# PrintNC_CNC_Breakout.net
KiCad netlist of a schematic drawn in Altium Designer
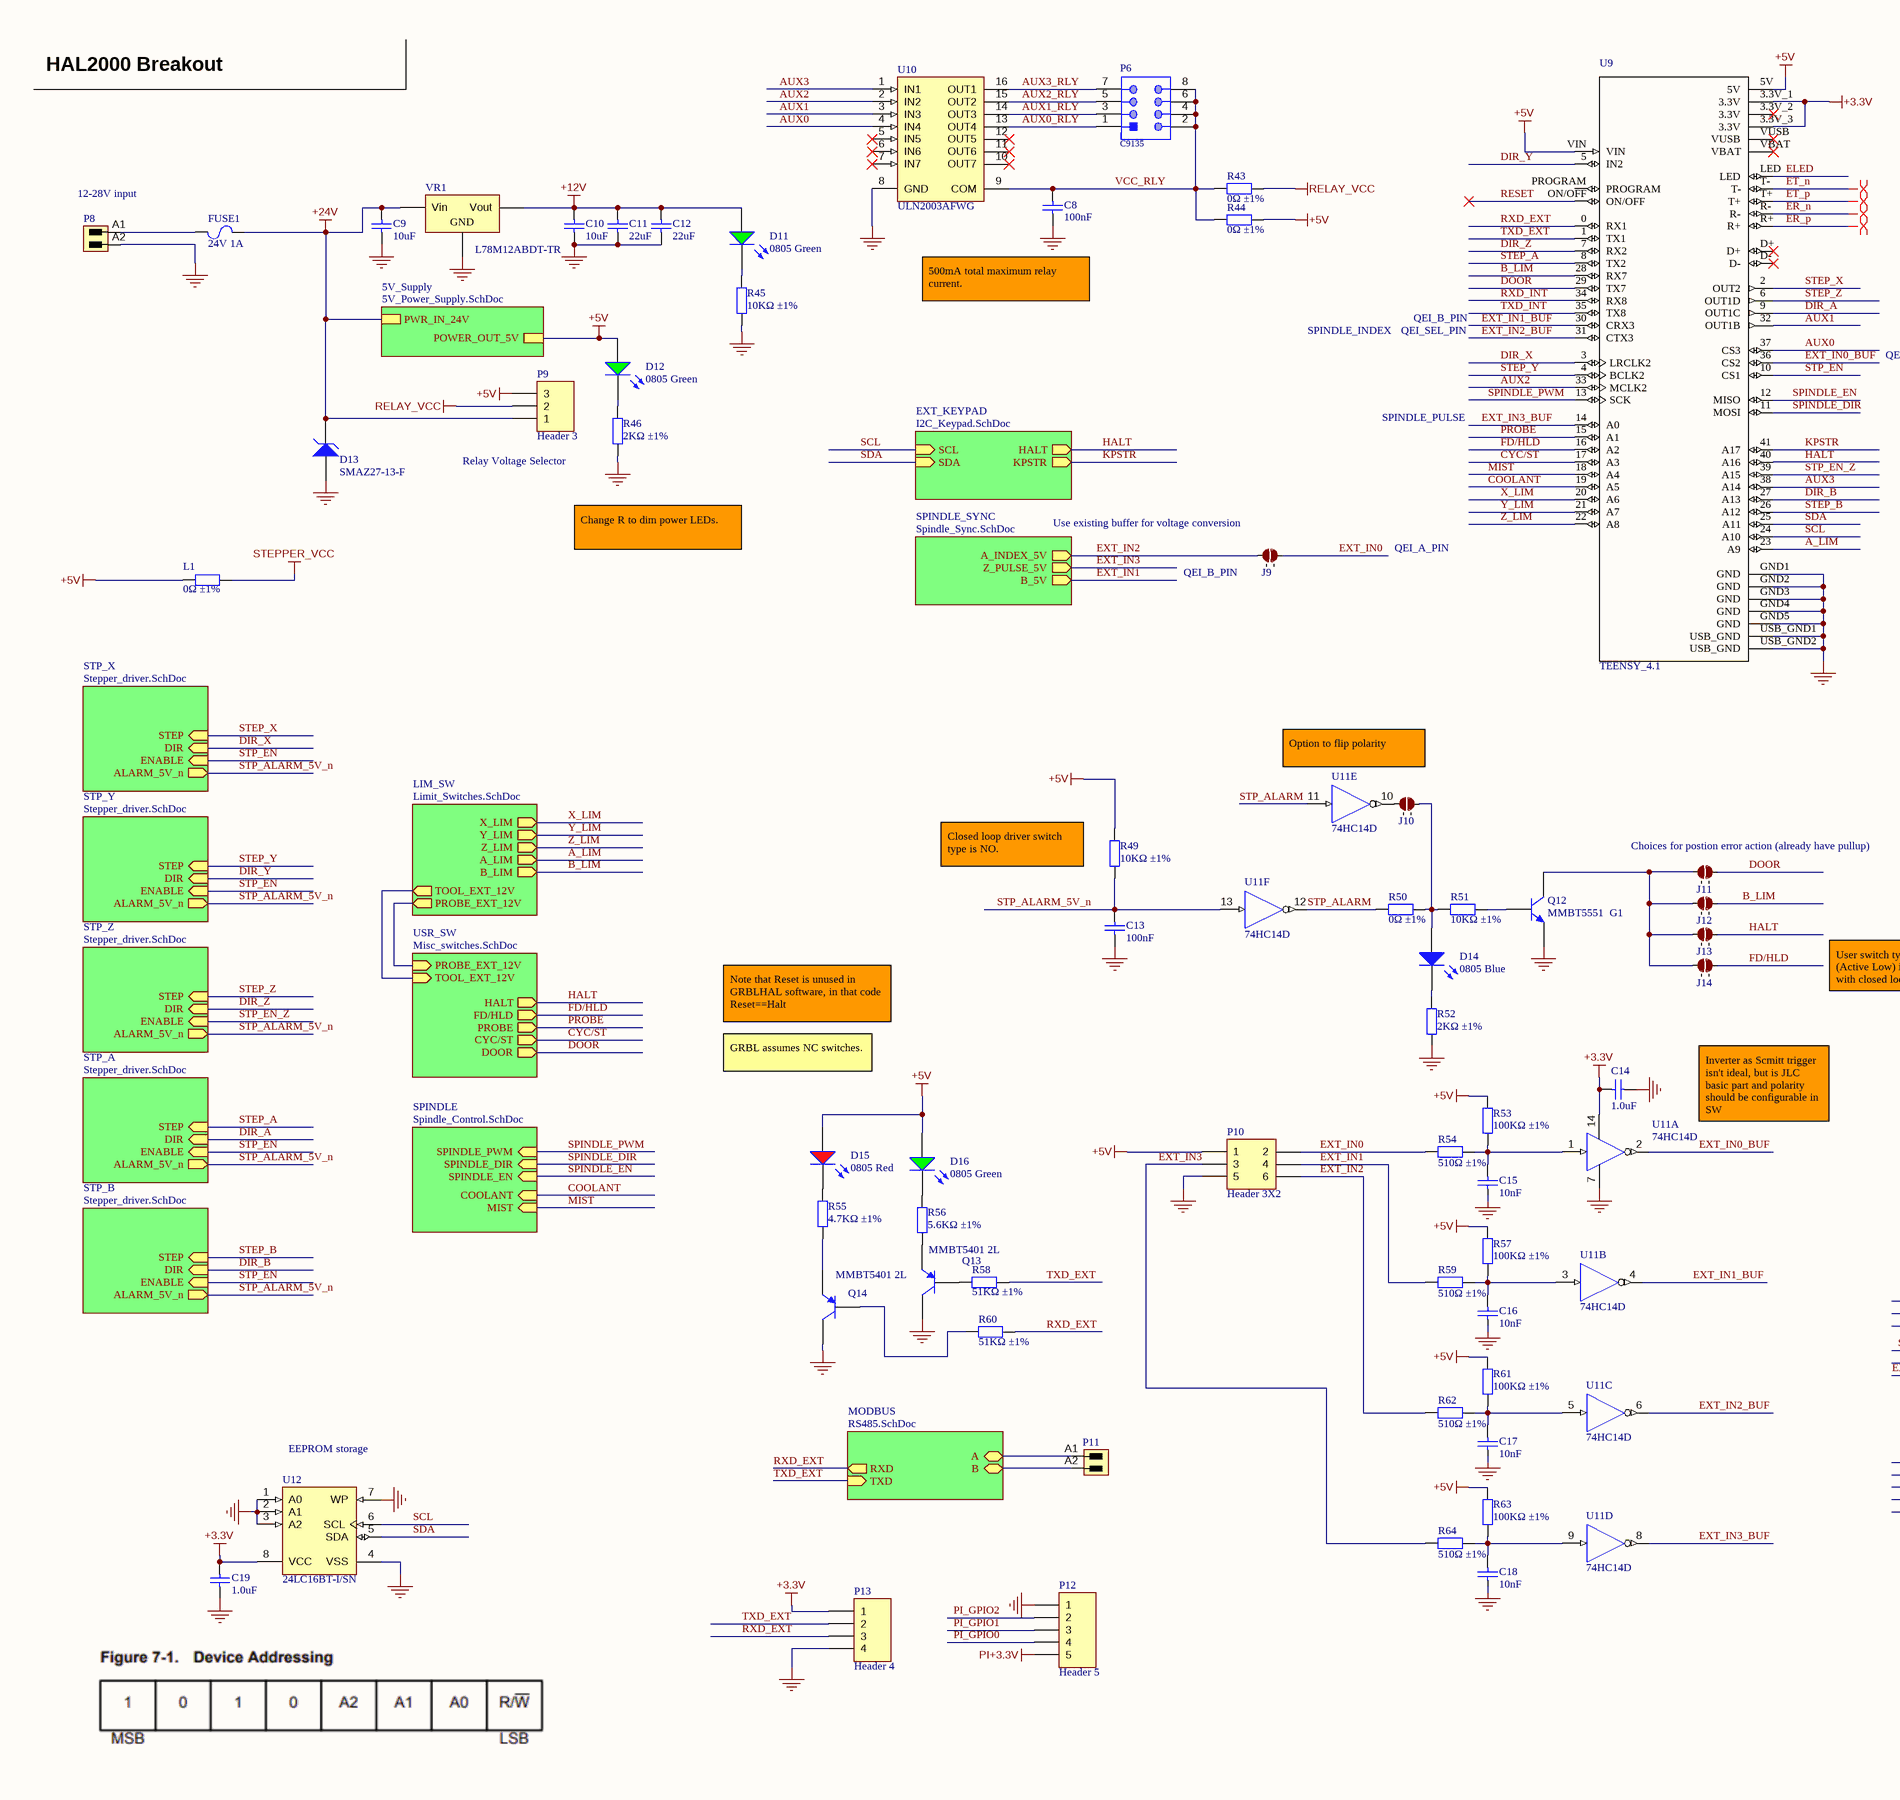
[diagram p0: PrintNC_CNC_Breakout.SchDoc, left]
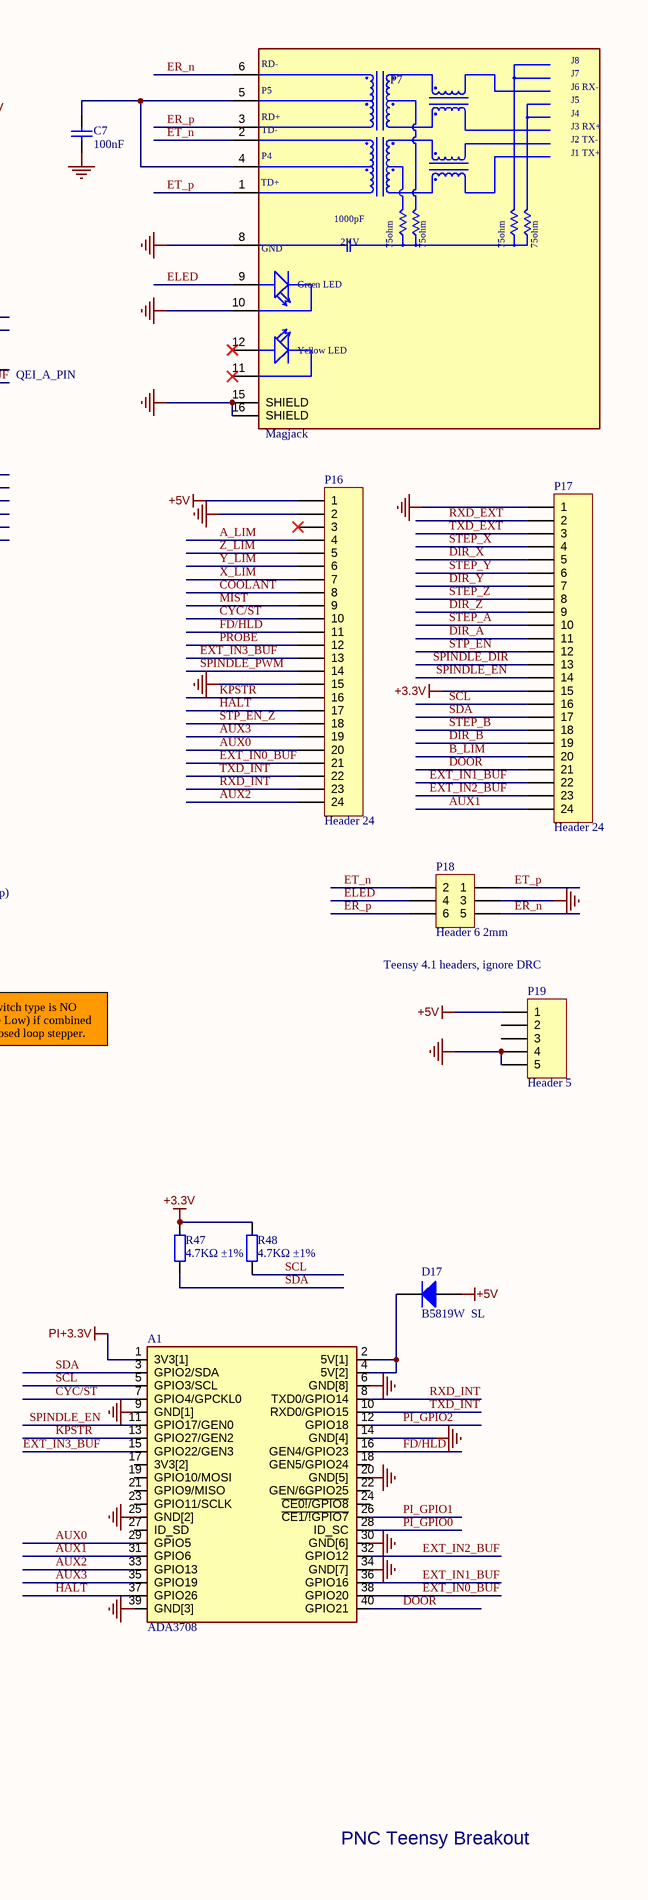
[diagram p1: PrintNC_CNC_Breakout.SchDoc, right]

(export (version "E")
  (design (tool "Eeschema 10.0.6"))
  (components
    (comp (ref "A1")
      (value "ADA3708")
      (footprint "ADA3708_RPI-ZERO")
      (description "Raspberry Pi Zero WH _Zero W with Headers_")
      (fields (field (name "MF") "Raspberry Pi"))
      (libsource (lib "Universal_CNC_Breakout") (part "ADA3708"))
    )
    (comp (ref "C7")
      (value "100nF")
      (footprint "1206_C")
      (description "Chip capacitors")
      (fields
        (field (name "MANUFACTURER") "Samsung Electro-Mechanics")
        (field (name "PARTNUMBER") "CL31B104KBCNNNC")
      )
      (libsource (lib "Cap") (part "1206 100nF (104) 10% 50V"))
    )
    (comp (ref "C8")
      (value "100nF")
      (footprint "0603_C")
      (description "Chip capacitors")
      (fields (field (name "MANUFACTURER") "YAGEO") (field (name "PARTNUMBER") "CC0603KRX7R9BB104"))
      (libsource (lib "Cap") (part "0603 100nF (104) 10% 50V"))
    )
    (comp (ref "C9")
      (value "10uF")
      (footprint "1206_C")
      (description "Chip capacitors")
      (fields
        (field (name "MANUFACTURER") "Samsung Electro-Mechanics")
        (field (name "PARTNUMBER") "CL31A106KBHNNNE")
      )
      (libsource (lib "Cap") (part "1206 10uF (106) 10% 50V"))
    )
    (comp (ref "C10")
      (value "10uF")
      (footprint "1206_C")
      (description "Chip capacitors")
      (fields
        (field (name "MANUFACTURER") "Samsung Electro-Mechanics")
        (field (name "PARTNUMBER") "CL31A106KBHNNNE")
      )
      (libsource (lib "Cap") (part "1206 10uF (106) 10% 50V"))
    )
    (comp (ref "C11")
      (value "22uF")
      (footprint "0805_C")
      (description "Chip capacitors")
      (fields
        (field (name "MANUFACTURER") "Samsung Electro-Mechanics")
        (field (name "PARTNUMBER") "CL21A226MAQNNNE")
      )
      (libsource (lib "Cap") (part "0805 22uF (226) 20% 25V"))
    )
    (comp (ref "C12")
      (value "22uF")
      (footprint "0805_C")
      (description "Chip capacitors")
      (fields
        (field (name "MANUFACTURER") "Samsung Electro-Mechanics")
        (field (name "PARTNUMBER") "CL21A226MAQNNNE")
      )
      (libsource (lib "Cap") (part "0805 22uF (226) 20% 25V"))
    )
    (comp (ref "C13")
      (value "100nF")
      (footprint "0402_C")
      (description "Chip capacitors")
      (fields
        (field (name "MANUFACTURER") "Samsung Electro-Mechanics")
        (field (name "PARTNUMBER") "CL05B104KO5NNNC")
      )
      (libsource (lib "Cap") (part "0402 100nF (104) 10% 16V"))
    )
    (comp (ref "C14")
      (value "1.0uF")
      (footprint "0402_C")
      (description "Chip capacitor")
      (fields
        (field (name "MANUFACTURER") "Samsung Electro-Mechanics")
        (field (name "PARTNUMBER") "CL05A105KA5NQNC")
      )
      (libsource (lib "Cap") (part "0402 1.0uF (105) 10% 25V"))
    )
    (comp (ref "C15")
      (value "10nF")
      (footprint "0402_C")
      (description "Chip capacitors")
      (fields
        (field (name "MANUFACTURER") "Samsung Electro-Mechanics")
        (field (name "PARTNUMBER") "CL05B103KB5NNNC")
      )
      (libsource (lib "Cap") (part "0402 10nF (103) 10% 50V"))
    )
    (comp (ref "C16")
      (value "10nF")
      (footprint "0402_C")
      (description "Chip capacitors")
      (fields
        (field (name "MANUFACTURER") "Samsung Electro-Mechanics")
        (field (name "PARTNUMBER") "CL05B103KB5NNNC")
      )
      (libsource (lib "Cap") (part "0402 10nF (103) 10% 50V"))
    )
    (comp (ref "C17")
      (value "10nF")
      (footprint "0402_C")
      (description "Chip capacitors")
      (fields
        (field (name "MANUFACTURER") "Samsung Electro-Mechanics")
        (field (name "PARTNUMBER") "CL05B103KB5NNNC")
      )
      (libsource (lib "Cap") (part "0402 10nF (103) 10% 50V"))
    )
    (comp (ref "C18")
      (value "10nF")
      (footprint "0402_C")
      (description "Chip capacitors")
      (fields
        (field (name "MANUFACTURER") "Samsung Electro-Mechanics")
        (field (name "PARTNUMBER") "CL05B103KB5NNNC")
      )
      (libsource (lib "Cap") (part "0402 10nF (103) 10% 50V"))
    )
    (comp (ref "C19")
      (value "1.0uF")
      (footprint "0402_C")
      (description "Chip capacitor")
      (fields
        (field (name "MANUFACTURER") "Samsung Electro-Mechanics")
        (field (name "PARTNUMBER") "CL05A105KA5NQNC")
      )
      (libsource (lib "Cap") (part "0402 1.0uF (105) 10% 25V"))
    )
    (comp (ref "D11")
      (value "0805 Green")
      (footprint "0805_LED_S1")
      (description "LED")
      (libsource (lib "LED") (part "0805 LED Green"))
    )
    (comp (ref "D12")
      (value "0805 Green")
      (footprint "0805_LED_S1")
      (description "LED")
      (libsource (lib "LED") (part "0805 LED Green"))
    )
    (comp (ref "D13")
      (value "SMAZ27-13-F")
      (footprint "DIOM5226X240N")
      (description "27V ±5% 1W 500nA @ 20.5V SMA(DO-214AC) Zener Diodes RoHS")
      (libsource (lib "PrintNC_GRBLHAL_Breakout") (part "BZT52C27"))
    )
    (comp (ref "D14")
      (value "0805 Blue")
      (footprint "0805_LED_S1")
      (description "LED")
      (libsource (lib "LED") (part "0805 LED Blue"))
    )
    (comp (ref "D15")
      (value "0805 Red")
      (footprint "0805_LED_S1")
      (description "LED")
      (fields
        (field (name "PARTNUMBER") "FC-2012HRK-620D")
        (field (name "MANUFACTURER") "Foshan NationStar Optoelectronics")
      )
      (libsource (lib "LED") (part "0805 LED Red"))
    )
    (comp (ref "D16")
      (value "0805 Green")
      (footprint "0805_LED_S1")
      (description "LED")
      (libsource (lib "LED") (part "0805 LED Green"))
    )
    (comp (ref "D17")
      (value "B5819W  SL")
      (footprint "SOD-123")
      (description "肖特基二极管")
      (libsource (lib "Diode") (part "SOD-123 B5819W  SL"))
    )
    (comp (ref "FUSE1")
      (value "24V 1A")
      (footprint "1206_C")
      (description "24V 1A 0.1s 1206 PTC Resettable Fuses RoHS")
      (fields
        (field (name "MANUFACTURER") "Jinrui Electronic Materials Co.")
        (field (name "PARTNUMBER") "JK-nSMD050-24")
      )
      (libsource (lib "PrintNC_GRBLHAL_Breakout") (part "JK-nSMD050-24"))
    )
    (comp (ref "J9")
      (value "2 way net solder junction - Normally Open")
      (footprint "2waySolder_NO")
      (libsource (lib "PrintNC_GRBLHAL_Breakout") (part "2waySolderNO"))
    )
    (comp (ref "J10")
      (value "2 way net solder junction - Normally Open")
      (footprint "2waySolder_NO")
      (libsource (lib "PrintNC_GRBLHAL_Breakout") (part "2waySolderNO"))
    )
    (comp (ref "J11")
      (value "2 way net solder junction - Normally Open")
      (footprint "2waySolder_NO")
      (libsource (lib "PrintNC_GRBLHAL_Breakout") (part "2waySolderNO"))
    )
    (comp (ref "J12")
      (value "2 way net solder junction - Normally Open")
      (footprint "2waySolder_NO")
      (libsource (lib "PrintNC_GRBLHAL_Breakout") (part "2waySolderNO"))
    )
    (comp (ref "J13")
      (value "2 way net solder junction - Normally Open")
      (footprint "2waySolder_NO")
      (libsource (lib "PrintNC_GRBLHAL_Breakout") (part "2waySolderNO"))
    )
    (comp (ref "J14")
      (value "2 way net solder junction - Normally Open")
      (footprint "2waySolder_NO")
      (libsource (lib "PrintNC_GRBLHAL_Breakout") (part "2waySolderNO"))
    )
    (comp (ref "L1")
      (value "0Ω ±1%")
      (footprint "0402_R")
      (description "Chip resistor")
      (fields (field (name "POWER") "1/16W") (field (name "MANUFACTURER") "Uniroyal Elec"))
      (libsource (lib "") (part "0402 0R (0R0) 1%_1"))
    )
    (comp (ref "P6")
      (value "C9135")
      (footprint "61200821621")
      (description "Male Box Header WR-BHD, THT, Vertical, pitch 2.54 mm, 8 pins")
      (fields (field (name "MANUFACTURER") "Wurth Elektronik") (field (name "PUBLISHER") "WurthElektronik"))
      (libsource (lib "PrintNC_GRBLHAL_Breakout") (part "WE-CN-2P-M-R8"))
    )
    (comp (ref "P7")
      (value "Magjack")
      (footprint "HANRUN_HR911105A")
      (description "HR911105A Ethernet Interface Arduino Platform Evaluation Expansion Board")
      (fields (field (name "MP") "HR911105A") (field (name "MF") "DFRobot"))
      (libsource (lib "PrintNC_GRBLHAL_Breakout") (part "HR911105A"))
    )
    (comp (ref "P8")
      (value "~")
      (footprint "SL_3_50_180G_02")
      (fields
        (field (name "PARTNUMBER") "WJ15EDGVC-3.5-2P")
        (field (name "MANUFACTURER") "Ningbo Kangnex Elec")
      )
      (libsource (lib "") (part "Header_Male_02_1x02_1"))
    )
    (comp (ref "P9")
      (value "Header 3")
      (footprint "HDR1X3")
      (description "Header, 3-Pin")
      (fields (field (name "PUBLISHER") "Altium Limited"))
      (libsource (lib "PrintNC_GRBLHAL_Breakout") (part "Header 3"))
    )
    (comp (ref "P10")
      (value "Header 3X2")
      (footprint "HDR2X3")
      (description "Header, 3-Pin, Dual row")
      (fields (field (name "PUBLISHER") "Altium Limited"))
      (libsource (lib "PrintNC_GRBLHAL_Breakout") (part "Header 3X2"))
    )
    (comp (ref "P11")
      (value "~")
      (footprint "SL_3_50_180G_02")
      (fields
        (field (name "PARTNUMBER") "WJ15EDGVC-3.5-2P")
        (field (name "MANUFACTURER") "Ningbo Kangnex Elec")
      )
      (libsource (lib "PrintNC_GRBLHAL_Breakout") (part "Header_Male_02_1x02"))
    )
    (comp (ref "P12")
      (value "Header 5")
      (footprint "HDR1X5")
      (description "Header, 5-Pin")
      (fields (field (name "PUBLISHER") "Altium Limited"))
      (libsource (lib "PrintNC_GRBLHAL_Breakout") (part "Header 5"))
    )
    (comp (ref "P13")
      (value "Header 4")
      (footprint "HDR1X4")
      (description "Header, 4-Pin")
      (fields (field (name "PUBLISHER") "Altium Limited"))
      (libsource (lib "PrintNC_GRBLHAL_Breakout") (part "Header 4"))
    )
    (comp (ref "P16")
      (value "Header 24")
      (footprint "HDR1X24")
      (description "Header, 24-Pin")
      (fields (field (name "PUBLISHER") "Altium Limited"))
      (libsource (lib "Miscellaneous Connectors") (part "Header 24"))
    )
    (comp (ref "P17")
      (value "Header 24")
      (footprint "HDR1X24")
      (description "Header, 24-Pin")
      (fields (field (name "PUBLISHER") "Altium Limited"))
      (libsource (lib "Miscellaneous Connectors") (part "Header 24"))
    )
    (comp (ref "P18")
      (value "Header 6 2mm")
      (footprint "HDR2X3 - 2mm")
      (description "Header, 6-Pin 2x3, 2mm pitch")
      (fields (field (name "PUBLISHER") "Altium Limited"))
      (libsource (lib "PrintNC_GRBLHAL_Breakout") (part "Header 6 2mm"))
    )
    (comp (ref "P19")
      (value "Header 5")
      (footprint "HDR1X5")
      (description "Header, 5-Pin")
      (fields (field (name "PUBLISHER") "Altium Limited"))
      (libsource (lib "PrintNC_GRBLHAL_Breakout") (part "Header 5"))
    )
    (comp (ref "Q12")
      (value "MMBT5551  G1")
      (footprint "SOT-23(SOT-23-3)")
      (description "三极管")
      (libsource (lib "PrintNC_GRBLHAL_Breakout") (part "SOT-23 MMBT5551  G1"))
    )
    (comp (ref "Q13")
      (value "MMBT5401 2L")
      (footprint "SOT-23(SOT-23-3)")
      (description "三极管")
      (libsource (lib "PrintNC_GRBLHAL_Breakout") (part "SOT-23 MMBT5401 2L"))
    )
    (comp (ref "Q14")
      (value "MMBT5401 2L")
      (footprint "SOT-23(SOT-23-3)")
      (description "三极管")
      (libsource (lib "PrintNC_GRBLHAL_Breakout") (part "SOT-23 MMBT5401 2L"))
    )
    (comp (ref "R43")
      (value "0Ω ±1%")
      (footprint "0402_R")
      (description "Chip resistor")
      (fields (field (name "POWER") "1/16W") (field (name "MANUFACTURER") "Uniroyal Elec"))
      (libsource (lib "PrintNC_GRBLHAL_Breakout") (part "0402 0R (0R0) 1%"))
    )
    (comp (ref "R44")
      (value "0Ω ±1%")
      (footprint "0402_R")
      (description "Chip resistor")
      (fields (field (name "POWER") "1/16W") (field (name "MANUFACTURER") "Uniroyal Elec"))
      (libsource (lib "PrintNC_GRBLHAL_Breakout") (part "0402 0R (0R0) 1%"))
    )
    (comp (ref "R45")
      (value "10KΩ ±1%")
      (footprint "0402_R")
      (description "Chip resistor")
      (fields (field (name "MANUFACTURER") "Uniroyal Elec") (field (name "PARTNUMBER") "0402WGF1002TCE"))
      (libsource (lib "PrintNC_GRBLHAL_Breakout") (part "0402 10K (1002) 1%"))
    )
    (comp (ref "R46")
      (value "2KΩ ±1%")
      (footprint "0402_R")
      (description "Chip resistor")
      (fields (field (name "MANUFACTURER") "Uniroyal Elec") (field (name "PARTNUMBER") "0402WGF2001TCE"))
      (libsource (lib "RES") (part "0402 2K (2001) 1%"))
    )
    (comp (ref "R47")
      (value "4.7KΩ ±1%")
      (footprint "0402_R")
      (description "Chip resistor")
      (fields (field (name "MANUFACTURER") "Uniroyal Elec") (field (name "PARTNUMBER") "0402WGF4701TCE"))
      (libsource (lib "RES") (part "0402 4.7K (4701) 1%"))
    )
    (comp (ref "R48")
      (value "4.7KΩ ±1%")
      (footprint "0402_R")
      (description "Chip resistor")
      (fields (field (name "MANUFACTURER") "Uniroyal Elec") (field (name "PARTNUMBER") "0402WGF4701TCE"))
      (libsource (lib "RES") (part "0402 4.7K (4701) 1%"))
    )
    (comp (ref "R49")
      (value "10KΩ ±1%")
      (footprint "0402_R")
      (description "Chip resistor")
      (fields (field (name "MANUFACTURER") "Uniroyal Elec") (field (name "PARTNUMBER") "0402WGF1002TCE"))
      (libsource (lib "PrintNC_GRBLHAL_Breakout") (part "0402 10K (1002) 1%"))
    )
    (comp (ref "R50")
      (value "0Ω ±1%")
      (footprint "0402_R")
      (description "Chip resistor")
      (fields (field (name "POWER") "1/16W") (field (name "MANUFACTURER") "Uniroyal Elec"))
      (libsource (lib "PrintNC_GRBLHAL_Breakout") (part "0402 0R (0R0) 1%"))
    )
    (comp (ref "R51")
      (value "10KΩ ±1%")
      (footprint "0402_R")
      (description "Chip resistor")
      (fields (field (name "MANUFACTURER") "Uniroyal Elec") (field (name "PARTNUMBER") "0402WGF1002TCE"))
      (libsource (lib "") (part "0402 10K (1002) 1%_1"))
    )
    (comp (ref "R52")
      (value "2KΩ ±1%")
      (footprint "0402_R")
      (description "Chip resistor")
      (fields (field (name "MANUFACTURER") "Uniroyal Elec") (field (name "PARTNUMBER") "0402WGF2001TCE"))
      (libsource (lib "PrintNC_GRBLHAL_Breakout") (part "0402 2K (2001) 1%"))
    )
    (comp (ref "R53")
      (value "100KΩ ±1%")
      (footprint "0402_R")
      (description "Chip resistor")
      (fields (field (name "MANUFACTURER") "Uniroyal Elec") (field (name "PARTNUMBER") "0402WGF1003TCE"))
      (libsource (lib "PrintNC_GRBLHAL_Breakout") (part "0402 100K (1003) 1%"))
    )
    (comp (ref "R54")
      (value "510Ω ±1%")
      (footprint "0402_R")
      (description "Chip resistor")
      (fields (field (name "MANUFACTURER") "Uniroyal Elec") (field (name "PARTNUMBER") "0402WGF5100TCE"))
      (libsource (lib "PrintNC_GRBLHAL_Breakout") (part "0402 510R (5100) 1%"))
    )
    (comp (ref "R55")
      (value "4.7KΩ ±1%")
      (footprint "0402_R")
      (description "Chip resistor")
      (fields (field (name "MANUFACTURER") "Uniroyal Elec") (field (name "PARTNUMBER") "0402WGF4701TCE"))
      (libsource (lib "PrintNC_GRBLHAL_Breakout") (part "0402 4.7K (4701) 1%"))
    )
    (comp (ref "R56")
      (value "5.6KΩ ±1%")
      (footprint "0402_R")
      (description "Chip resistor")
      (fields (field (name "MANUFACTURER") "Uniroyal Elec") (field (name "PARTNUMBER") "0402WGF5601TCE"))
      (libsource (lib "PrintNC_GRBLHAL_Breakout") (part "0402 5.6K (5601) 1%"))
    )
    (comp (ref "R57")
      (value "100KΩ ±1%")
      (footprint "0402_R")
      (description "Chip resistor")
      (fields (field (name "MANUFACTURER") "Uniroyal Elec") (field (name "PARTNUMBER") "0402WGF1003TCE"))
      (libsource (lib "PrintNC_GRBLHAL_Breakout") (part "0402 100K (1003) 1%"))
    )
    (comp (ref "R58")
      (value "51KΩ ±1%")
      (footprint "0402_R")
      (description "Chip resistor")
      (fields (field (name "MANUFACTURER") "Uniroyal Elec") (field (name "PARTNUMBER") "0402WGF5102TCE"))
      (libsource (lib "PrintNC_GRBLHAL_Breakout") (part "0402 51K (5102) 1%"))
    )
    (comp (ref "R59")
      (value "510Ω ±1%")
      (footprint "0402_R")
      (description "Chip resistor")
      (fields (field (name "MANUFACTURER") "Uniroyal Elec") (field (name "PARTNUMBER") "0402WGF5100TCE"))
      (libsource (lib "PrintNC_GRBLHAL_Breakout") (part "0402 510R (5100) 1%"))
    )
    (comp (ref "R60")
      (value "51KΩ ±1%")
      (footprint "0402_R")
      (description "Chip resistor")
      (fields (field (name "MANUFACTURER") "Uniroyal Elec") (field (name "PARTNUMBER") "0402WGF5102TCE"))
      (libsource (lib "") (part "0402 51K (5102) 1%_1"))
    )
    (comp (ref "R61")
      (value "100KΩ ±1%")
      (footprint "0402_R")
      (description "Chip resistor")
      (fields (field (name "MANUFACTURER") "Uniroyal Elec") (field (name "PARTNUMBER") "0402WGF1003TCE"))
      (libsource (lib "PrintNC_GRBLHAL_Breakout") (part "0402 100K (1003) 1%"))
    )
    (comp (ref "R62")
      (value "510Ω ±1%")
      (footprint "0402_R")
      (description "Chip resistor")
      (fields (field (name "MANUFACTURER") "Uniroyal Elec") (field (name "PARTNUMBER") "0402WGF5100TCE"))
      (libsource (lib "PrintNC_GRBLHAL_Breakout") (part "0402 510R (5100) 1%"))
    )
    (comp (ref "R63")
      (value "100KΩ ±1%")
      (footprint "0402_R")
      (description "Chip resistor")
      (fields (field (name "MANUFACTURER") "Uniroyal Elec") (field (name "PARTNUMBER") "0402WGF1003TCE"))
      (libsource (lib "PrintNC_GRBLHAL_Breakout") (part "0402 100K (1003) 1%"))
    )
    (comp (ref "R64")
      (value "510Ω ±1%")
      (footprint "0402_R")
      (description "Chip resistor")
      (fields (field (name "MANUFACTURER") "Uniroyal Elec") (field (name "PARTNUMBER") "0402WGF5100TCE"))
      (libsource (lib "PrintNC_GRBLHAL_Breakout") (part "0402 510R (5100) 1%"))
    )
    (comp (ref "U9")
      (value "TEENSY_4.1")
      (footprint "TEENSY4-1")
      (description "None")
      (libsource (lib "PrintNC_GRBLHAL_Breakout") (part "DEV-16771"))
    )
    (comp (ref "U10")
      (value "ULN2003AFWG")
      (footprint "SOIC-16_150mil")
      (description "大电流驱动")
      (libsource (lib "PrintNC_GRBLHAL_Breakout") (part "ULN2003AFWG_[C5437]"))
    )
    (comp (ref "U11")
      (value "74HC14D")
      (footprint "SOIC-14_150mil")
      (description "74系列逻辑芯片")
      (libsource (lib "PrintNC_GRBLHAL_Breakout") (part "74HC14D_[C5605]"))
    )
    (comp (ref "U12")
      (value "24LC16BT-I/SN")
      (footprint "SOIC-SN8_L")
      (description "IC EEPROM 16KBIT I2C 8SOIC")
      (libsource (lib "PrintNC_GRBLHAL_Breakout") (part "MEM-SEEPROM-34AA02-IL8"))
    )
    (comp (ref "VR1")
      (value "L78M12ABDT-TR")
      (footprint "TO-252-2-180")
      (description "DNI")
      (libsource (lib "PrintNC_GRBLHAL_Breakout") (part "TO-252-2 L78M05ABDT-TR"))
    )
  )
  (nets
    (net (code "1") (name "+3.3V") (class "Default")
      (node (ref "C14") (pin "1") (pinfunction "1_1") (pintype "passive"))
      (node (ref "C19") (pin "2") (pinfunction "2_2") (pintype "passive"))
      (node (ref "P13") (pin "1") (pinfunction "1_1") (pintype "passive"))
      (node (ref "P17") (pin "15") (pinfunction "15_15") (pintype "passive"))
      (node (ref "R47") (pin "2") (pinfunction "2_2") (pintype "passive"))
      (node (ref "R48") (pin "2") (pinfunction "2_2") (pintype "passive"))
      (node (ref "U11") (pin "14") (pinfunction "VCC_14") (pintype "power_in"))
      (node (ref "U12") (pin "8") (pinfunction "VCC_8") (pintype "power_in"))
      (node (ref "U9") (pin "3.3V_1") (pinfunction "3.3V_3.3V_1") (pintype "power_in"))
      (node (ref "U9") (pin "3.3V_3") (pinfunction "3.3V_3.3V_3") (pintype "power_in"))
    )
    (net (code "2") (name "+5V") (class "Default")
      (node (ref "D12") (pin "A") (pinfunction "A_A") (pintype "passive"))
      (node (ref "D15") (pin "A") (pinfunction "A_A") (pintype "passive"))
      (node (ref "D16") (pin "A") (pinfunction "A_A") (pintype "passive"))
      (node (ref "D17") (pin "1") (pinfunction "A_1") (pintype "passive"))
      (node (ref "L1") (pin "1") (pinfunction "1_1") (pintype "passive"))
      (node (ref "P10") (pin "1") (pinfunction "1_1") (pintype "passive"))
      (node (ref "P16") (pin "1") (pinfunction "1_1") (pintype "passive"))
      (node (ref "P19") (pin "1") (pinfunction "1_1") (pintype "passive"))
      (node (ref "P9") (pin "3") (pinfunction "3_3") (pintype "passive"))
      (node (ref "R44") (pin "1") (pinfunction "1_1") (pintype "passive"))
      (node (ref "R49") (pin "2") (pinfunction "2_2") (pintype "passive"))
      (node (ref "R53") (pin "2") (pinfunction "2_2") (pintype "passive"))
      (node (ref "R57") (pin "2") (pinfunction "2_2") (pintype "passive"))
      (node (ref "R61") (pin "2") (pinfunction "2_2") (pintype "passive"))
      (node (ref "R63") (pin "2") (pinfunction "2_2") (pintype "passive"))
      (node (ref "U9") (pin "5V") (pinfunction "5V_5V") (pintype "power_in"))
      (node (ref "U9") (pin "VIN") (pinfunction "VIN_VIN") (pintype "input"))
    )
    (net (code "3") (name "+12V") (class "Default")
      (node (ref "C10") (pin "2") (pinfunction "2_2") (pintype "passive"))
      (node (ref "C11") (pin "2") (pinfunction "2_2") (pintype "passive"))
      (node (ref "C12") (pin "2") (pinfunction "2_2") (pintype "passive"))
      (node (ref "D11") (pin "A") (pinfunction "A_A") (pintype "passive"))
      (node (ref "VR1") (pin "3") (pinfunction "Vout_3") (pintype "passive"))
    )
    (net (code "4") (name "+24V") (class "Default")
      (node (ref "C9") (pin "2") (pinfunction "2_2") (pintype "passive"))
      (node (ref "D13") (pin "2") (pinfunction "K_2") (pintype "passive"))
      (node (ref "FUSE1") (pin "2") (pinfunction "2_2") (pintype "passive"))
      (node (ref "P9") (pin "1") (pinfunction "1_1") (pintype "passive"))
      (node (ref "VR1") (pin "1") (pinfunction "Vin_1") (pintype "passive"))
    )
    (net (code "5") (name "/A") (class "Default")
      (node (ref "P11") (pin "A1") (pinfunction "A1_A1") (pintype "passive"))
    )
    (net (code "6") (name "/AUX0") (class "Default")
      (node (ref "A1") (pin "29") (pinfunction "GPIO5_29") (pintype "bidirectional"))
      (node (ref "P16") (pin "20") (pinfunction "20_20") (pintype "passive"))
      (node (ref "U10") (pin "4") (pinfunction "IN4_4") (pintype "input"))
      (node (ref "U9") (pin "37") (pinfunction "CS3_37") (pintype "bidirectional"))
    )
    (net (code "7") (name "/AUX0_RLY") (class "Default")
      (node (ref "P6") (pin "1") (pinfunction "1_1") (pintype "passive"))
      (node (ref "U10") (pin "13") (pinfunction "OUT4_13") (pintype "open_collector"))
    )
    (net (code "8") (name "/AUX1") (class "Default")
      (node (ref "A1") (pin "31") (pinfunction "GPIO6_31") (pintype "bidirectional"))
      (node (ref "P17") (pin "24") (pinfunction "24_24") (pintype "passive"))
      (node (ref "U10") (pin "3") (pinfunction "IN3_3") (pintype "input"))
      (node (ref "U9") (pin "32") (pinfunction "OUT1B_32") (pintype "output"))
    )
    (net (code "9") (name "/AUX1_RLY") (class "Default")
      (node (ref "P6") (pin "3") (pinfunction "3_3") (pintype "passive"))
      (node (ref "U10") (pin "14") (pinfunction "OUT3_14") (pintype "open_collector"))
    )
    (net (code "10") (name "/AUX2") (class "Default")
      (node (ref "A1") (pin "33") (pinfunction "GPIO13_33") (pintype "bidirectional"))
      (node (ref "P16") (pin "24") (pinfunction "24_24") (pintype "passive"))
      (node (ref "U10") (pin "2") (pinfunction "IN2_2") (pintype "input"))
      (node (ref "U9") (pin "33") (pinfunction "MCLK2_33") (pintype "bidirectional"))
    )
    (net (code "11") (name "/AUX2_RLY") (class "Default")
      (node (ref "P6") (pin "5") (pinfunction "5_5") (pintype "passive"))
      (node (ref "U10") (pin "15") (pinfunction "OUT2_15") (pintype "open_collector"))
    )
    (net (code "12") (name "/AUX3") (class "Default")
      (node (ref "A1") (pin "35") (pinfunction "GPIO19_35") (pintype "bidirectional"))
      (node (ref "P16") (pin "19") (pinfunction "19_19") (pintype "passive"))
      (node (ref "U10") (pin "1") (pinfunction "IN1_1") (pintype "input"))
      (node (ref "U9") (pin "38") (pinfunction "A14_38") (pintype "bidirectional"))
    )
    (net (code "13") (name "/AUX3_RLY") (class "Default")
      (node (ref "P6") (pin "7") (pinfunction "7_7") (pintype "passive"))
      (node (ref "U10") (pin "16") (pinfunction "OUT1_16") (pintype "open_collector"))
    )
    (net (code "14") (name "/A_LIM") (class "Default")
      (node (ref "P16") (pin "4") (pinfunction "4_4") (pintype "passive"))
      (node (ref "U9") (pin "23") (pinfunction "A9_23") (pintype "bidirectional"))
    )
    (net (code "15") (name "/B") (class "Default")
      (node (ref "P11") (pin "A2") (pinfunction "A2_A2") (pintype "passive"))
    )
    (net (code "16") (name "/B_LIM") (class "Default")
      (node (ref "J12") (pin "2") (pinfunction "2_2") (pintype "passive"))
      (node (ref "P17") (pin "20") (pinfunction "20_20") (pintype "passive"))
      (node (ref "U9") (pin "28") (pinfunction "RX7_28") (pintype "bidirectional"))
    )
    (net (code "17") (name "/COOLANT") (class "Default")
      (node (ref "P16") (pin "8") (pinfunction "8_8") (pintype "passive"))
      (node (ref "U9") (pin "19") (pinfunction "A5_19") (pintype "bidirectional"))
    )
    (net (code "18") (name "/CYC{slash}ST") (class "Default")
      (node (ref "A1") (pin "7") (pinfunction "GPIO4/GPCKL0_7") (pintype "bidirectional"))
      (node (ref "P16") (pin "10") (pinfunction "10_10") (pintype "passive"))
      (node (ref "U9") (pin "17") (pinfunction "A3_17") (pintype "bidirectional"))
    )
    (net (code "19") (name "/DIR_A") (class "Default")
      (node (ref "P17") (pin "11") (pinfunction "11_11") (pintype "passive"))
      (node (ref "U9") (pin "9") (pinfunction "OUT1C_9") (pintype "output"))
    )
    (net (code "20") (name "/DIR_B") (class "Default")
      (node (ref "P17") (pin "19") (pinfunction "19_19") (pintype "passive"))
      (node (ref "U9") (pin "27") (pinfunction "A13_27") (pintype "bidirectional"))
    )
    (net (code "21") (name "/DIR_X") (class "Default")
      (node (ref "P17") (pin "5") (pinfunction "5_5") (pintype "passive"))
      (node (ref "U9") (pin "3") (pinfunction "LRCLK2_3") (pintype "bidirectional"))
    )
    (net (code "22") (name "/DIR_Y") (class "Default")
      (node (ref "P17") (pin "7") (pinfunction "7_7") (pintype "passive"))
      (node (ref "U9") (pin "5") (pinfunction "IN2_5") (pintype "bidirectional"))
    )
    (net (code "23") (name "/DIR_Z") (class "Default")
      (node (ref "P17") (pin "9") (pinfunction "9_9") (pintype "passive"))
      (node (ref "U9") (pin "7") (pinfunction "RX2_7") (pintype "bidirectional"))
    )
    (net (code "24") (name "/DOOR") (class "Default")
      (node (ref "A1") (pin "40") (pinfunction "GPIO21_40") (pintype "bidirectional"))
      (node (ref "J11") (pin "2") (pinfunction "2_2") (pintype "passive"))
      (node (ref "P17") (pin "21") (pinfunction "21_21") (pintype "passive"))
      (node (ref "U9") (pin "29") (pinfunction "TX7_29") (pintype "bidirectional"))
    )
    (net (code "25") (name "/ELED") (class "Default")
      (node (ref "P18") (pin "4") (pinfunction "4_4") (pintype "passive"))
      (node (ref "P7") (pin "9") (pinfunction "GA_9") (pintype "passive"))
      (node (ref "U9") (pin "LED") (pinfunction "LED_LED") (pintype "bidirectional"))
    )
    (net (code "26") (name "/ER_n") (class "Default")
      (node (ref "P18") (pin "5") (pinfunction "5_5") (pintype "passive"))
      (node (ref "P7") (pin "6") (pinfunction "RD-_6") (pintype "passive"))
      (node (ref "U9") (pin "R-") (pinfunction "R-_R-") (pintype "bidirectional"))
    )
    (net (code "27") (name "/ER_p") (class "Default")
      (node (ref "P18") (pin "6") (pinfunction "6_6") (pintype "passive"))
      (node (ref "P7") (pin "3") (pinfunction "RD+_3") (pintype "passive"))
      (node (ref "U9") (pin "R+") (pinfunction "R+_R+") (pintype "bidirectional"))
    )
    (net (code "28") (name "/ET_n") (class "Default")
      (node (ref "P18") (pin "2") (pinfunction "2_2") (pintype "passive"))
      (node (ref "P7") (pin "2") (pinfunction "TD-_2") (pintype "passive"))
      (node (ref "U9") (pin "T-") (pinfunction "T-_T-") (pintype "bidirectional"))
    )
    (net (code "29") (name "/ET_p") (class "Default")
      (node (ref "P18") (pin "1") (pinfunction "1_1") (pintype "passive"))
      (node (ref "P7") (pin "1") (pinfunction "TD+_1") (pintype "passive"))
      (node (ref "U9") (pin "T+") (pinfunction "T+_T+") (pintype "bidirectional"))
    )
    (net (code "30") (name "/EXT_IN0") (class "Default")
      (node (ref "J9") (pin "2") (pinfunction "2_2") (pintype "passive"))
      (node (ref "P10") (pin "2") (pinfunction "2_2") (pintype "passive"))
      (node (ref "R54") (pin "1") (pinfunction "1_1") (pintype "passive"))
    )
    (net (code "31") (name "/EXT_IN0_BUF") (class "Default")
      (node (ref "A1") (pin "38") (pinfunction "GPIO20_38") (pintype "bidirectional"))
      (node (ref "P16") (pin "21") (pinfunction "21_21") (pintype "passive"))
      (node (ref "U11") (pin "2") (pinfunction "Y_2") (pintype "output"))
      (node (ref "U9") (pin "36") (pinfunction "CS2_36") (pintype "bidirectional"))
    )
    (net (code "32") (name "/EXT_IN1") (class "Default")
      (node (ref "P10") (pin "4") (pinfunction "4_4") (pintype "passive"))
      (node (ref "R59") (pin "1") (pinfunction "1_1") (pintype "passive"))
    )
    (net (code "33") (name "/EXT_IN1_BUF") (class "Default")
      (node (ref "A1") (pin "36") (pinfunction "GPIO16_36") (pintype "bidirectional"))
      (node (ref "P17") (pin "22") (pinfunction "22_22") (pintype "passive"))
      (node (ref "U11") (pin "4") (pinfunction "Y_4") (pintype "output"))
      (node (ref "U9") (pin "30") (pinfunction "CRX3_30") (pintype "bidirectional"))
    )
    (net (code "34") (name "/EXT_IN2") (class "Default")
      (node (ref "J9") (pin "1") (pinfunction "1_1") (pintype "passive"))
      (node (ref "P10") (pin "6") (pinfunction "6_6") (pintype "passive"))
      (node (ref "R62") (pin "1") (pinfunction "1_1") (pintype "passive"))
    )
    (net (code "35") (name "/EXT_IN2_BUF") (class "Default")
      (node (ref "A1") (pin "32") (pinfunction "GPIO12_32") (pintype "bidirectional"))
      (node (ref "P17") (pin "23") (pinfunction "23_23") (pintype "passive"))
      (node (ref "U11") (pin "6") (pinfunction "Y_6") (pintype "output"))
      (node (ref "U9") (pin "31") (pinfunction "CTX3_31") (pintype "bidirectional"))
    )
    (net (code "36") (name "/EXT_IN3") (class "Default")
      (node (ref "P10") (pin "3") (pinfunction "3_3") (pintype "passive"))
      (node (ref "R64") (pin "1") (pinfunction "1_1") (pintype "passive"))
    )
    (net (code "37") (name "/EXT_IN3_BUF") (class "Default")
      (node (ref "A1") (pin "15") (pinfunction "GPIO22/GEN3_15") (pintype "bidirectional"))
      (node (ref "P16") (pin "13") (pinfunction "13_13") (pintype "passive"))
      (node (ref "U11") (pin "8") (pinfunction "Y_8") (pintype "output"))
      (node (ref "U9") (pin "14") (pinfunction "A0_14") (pintype "bidirectional"))
    )
    (net (code "38") (name "/FD{slash}HLD") (class "Default")
      (node (ref "A1") (pin "16") (pinfunction "GEN4/GPIO23_16") (pintype "bidirectional"))
      (node (ref "J14") (pin "2") (pinfunction "2_2") (pintype "passive"))
      (node (ref "P16") (pin "11") (pinfunction "11_11") (pintype "passive"))
      (node (ref "U9") (pin "16") (pinfunction "A2_16") (pintype "bidirectional"))
    )
    (net (code "39") (name "/HALT") (class "Default")
      (node (ref "A1") (pin "37") (pinfunction "GPIO26_37") (pintype "bidirectional"))
      (node (ref "J13") (pin "2") (pinfunction "2_2") (pintype "passive"))
      (node (ref "P16") (pin "17") (pinfunction "17_17") (pintype "passive"))
      (node (ref "U9") (pin "40") (pinfunction "A16_40") (pintype "bidirectional"))
    )
    (net (code "40") (name "/KPSTR") (class "Default")
      (node (ref "A1") (pin "13") (pinfunction "GPIO27/GEN2_13") (pintype "bidirectional"))
      (node (ref "P16") (pin "16") (pinfunction "16_16") (pintype "passive"))
      (node (ref "U9") (pin "41") (pinfunction "A17_41") (pintype "bidirectional"))
    )
    (net (code "41") (name "/MIST") (class "Default")
      (node (ref "P16") (pin "9") (pinfunction "9_9") (pintype "passive"))
      (node (ref "U9") (pin "18") (pinfunction "A4_18") (pintype "bidirectional"))
    )
    (net (code "42") (name "/PI_GPIO0") (class "Default")
      (node (ref "A1") (pin "28") (pinfunction "ID_SC_28") (pintype "bidirectional"))
      (node (ref "P12") (pin "4") (pinfunction "4_4") (pintype "passive"))
    )
    (net (code "43") (name "/PI_GPIO1") (class "Default")
      (node (ref "A1") (pin "26") (pinfunction "~{CE1/!GPIO7}_26") (pintype "bidirectional"))
      (node (ref "P12") (pin "3") (pinfunction "3_3") (pintype "passive"))
    )
    (net (code "44") (name "/PI_GPIO2") (class "Default")
      (node (ref "A1") (pin "12") (pinfunction "GPIO18_12") (pintype "bidirectional"))
      (node (ref "P12") (pin "2") (pinfunction "2_2") (pintype "passive"))
    )
    (net (code "45") (name "/PROBE") (class "Default")
      (node (ref "P16") (pin "12") (pinfunction "12_12") (pintype "passive"))
      (node (ref "U9") (pin "15") (pinfunction "A1_15") (pintype "bidirectional"))
    )
    (net (code "47") (name "/RESET") (class "Default")
      (node (ref "U9") (pin "ON/OFF") (pinfunction "ON/OFF_ON/OFF") (pintype "bidirectional+no_connect"))
    )
    (net (code "48") (name "/RXD_EXT") (class "Default")
      (node (ref "P13") (pin "3") (pinfunction "3_3") (pintype "passive"))
      (node (ref "P17") (pin "2") (pinfunction "2_2") (pintype "passive"))
      (node (ref "R60") (pin "1") (pinfunction "1_1") (pintype "passive"))
      (node (ref "U9") (pin "0") (pinfunction "RX1_0") (pintype "bidirectional"))
    )
    (net (code "49") (name "/RXD_INT") (class "Default")
      (node (ref "A1") (pin "8") (pinfunction "TXD0/GPIO14_8") (pintype "bidirectional"))
      (node (ref "P16") (pin "23") (pinfunction "23_23") (pintype "passive"))
      (node (ref "U9") (pin "34") (pinfunction "RX8_34") (pintype "bidirectional"))
    )
    (net (code "50") (name "/SCL") (class "Default")
      (node (ref "A1") (pin "5") (pinfunction "GPIO3/SCL_5") (pintype "bidirectional"))
      (node (ref "P17") (pin "16") (pinfunction "16_16") (pintype "passive"))
      (node (ref "R48") (pin "1") (pinfunction "1_1") (pintype "passive"))
      (node (ref "U12") (pin "6") (pinfunction "SCL_6") (pintype "input"))
      (node (ref "U9") (pin "24") (pinfunction "A10_24") (pintype "bidirectional"))
    )
    (net (code "51") (name "/SDA") (class "Default")
      (node (ref "A1") (pin "3") (pinfunction "GPIO2/SDA_3") (pintype "bidirectional"))
      (node (ref "P17") (pin "17") (pinfunction "17_17") (pintype "passive"))
      (node (ref "R47") (pin "1") (pinfunction "1_1") (pintype "passive"))
      (node (ref "U12") (pin "5") (pinfunction "SDA_5") (pintype "bidirectional"))
      (node (ref "U9") (pin "25") (pinfunction "A11_25") (pintype "bidirectional"))
    )
    (net (code "52") (name "/SPINDLE_DIR") (class "Default")
      (node (ref "P17") (pin "13") (pinfunction "13_13") (pintype "passive"))
      (node (ref "U9") (pin "11") (pinfunction "MOSI_11") (pintype "bidirectional"))
    )
    (net (code "53") (name "/SPINDLE_EN") (class "Default")
      (node (ref "A1") (pin "11") (pinfunction "GPIO17/GEN0_11") (pintype "bidirectional"))
      (node (ref "P17") (pin "14") (pinfunction "14_14") (pintype "passive"))
      (node (ref "U9") (pin "12") (pinfunction "MISO_12") (pintype "bidirectional"))
    )
    (net (code "54") (name "/SPINDLE_PWM") (class "Default")
      (node (ref "P16") (pin "14") (pinfunction "14_14") (pintype "passive"))
      (node (ref "U9") (pin "13") (pinfunction "SCK_13") (pintype "bidirectional"))
    )
    (net (code "55") (name "/STEP_A") (class "Default")
      (node (ref "P17") (pin "10") (pinfunction "10_10") (pintype "passive"))
      (node (ref "U9") (pin "8") (pinfunction "TX2_8") (pintype "bidirectional"))
    )
    (net (code "56") (name "/STEP_B") (class "Default")
      (node (ref "P17") (pin "18") (pinfunction "18_18") (pintype "passive"))
      (node (ref "U9") (pin "26") (pinfunction "A12_26") (pintype "bidirectional"))
    )
    (net (code "57") (name "/STEP_X") (class "Default")
      (node (ref "P17") (pin "4") (pinfunction "4_4") (pintype "passive"))
      (node (ref "U9") (pin "2") (pinfunction "OUT2_2") (pintype "output"))
    )
    (net (code "58") (name "/STEP_Y") (class "Default")
      (node (ref "P17") (pin "6") (pinfunction "6_6") (pintype "passive"))
      (node (ref "U9") (pin "4") (pinfunction "BCLK2_4") (pintype "bidirectional"))
    )
    (net (code "59") (name "/STEP_Z") (class "Default")
      (node (ref "P17") (pin "8") (pinfunction "8_8") (pintype "passive"))
      (node (ref "U9") (pin "6") (pinfunction "OUT1D_6") (pintype "output"))
    )
    (net (code "60") (name "/STP_ALARM") (class "Default")
      (node (ref "R50") (pin "2") (pinfunction "2_2") (pintype "passive"))
      (node (ref "U11") (pin "11") (pinfunction "A_11") (pintype "input"))
      (node (ref "U11") (pin "12") (pinfunction "Y_12") (pintype "output"))
    )
    (net (code "61") (name "/STP_ALARM_5V_n") (class "Default")
      (node (ref "C13") (pin "2") (pinfunction "2_2") (pintype "passive"))
      (node (ref "R49") (pin "1") (pinfunction "1_1") (pintype "passive"))
      (node (ref "U11") (pin "13") (pinfunction "A_13") (pintype "input"))
    )
    (net (code "62") (name "/STP_EN") (class "Default")
      (node (ref "P17") (pin "12") (pinfunction "12_12") (pintype "passive"))
      (node (ref "U9") (pin "10") (pinfunction "CS1_10") (pintype "bidirectional"))
    )
    (net (code "63") (name "/STP_EN_Z") (class "Default")
      (node (ref "P16") (pin "18") (pinfunction "18_18") (pintype "passive"))
      (node (ref "U9") (pin "39") (pinfunction "A15_39") (pintype "bidirectional"))
    )
    (net (code "65") (name "/TXD_EXT") (class "Default")
      (node (ref "P13") (pin "2") (pinfunction "2_2") (pintype "passive"))
      (node (ref "P17") (pin "3") (pinfunction "3_3") (pintype "passive"))
      (node (ref "R58") (pin "2") (pinfunction "2_2") (pintype "passive"))
      (node (ref "U9") (pin "1") (pinfunction "TX1_1") (pintype "bidirectional"))
    )
    (net (code "66") (name "/TXD_INT") (class "Default")
      (node (ref "A1") (pin "10") (pinfunction "RXD0/GPIO15_10") (pintype "bidirectional"))
      (node (ref "P16") (pin "22") (pinfunction "22_22") (pintype "passive"))
      (node (ref "U9") (pin "35") (pinfunction "TX8_35") (pintype "bidirectional"))
    )
    (net (code "67") (name "/VCC_RLY") (class "Default")
      (node (ref "C8") (pin "2") (pinfunction "2_2") (pintype "passive"))
      (node (ref "P6") (pin "2") (pinfunction "2_2") (pintype "passive"))
      (node (ref "P6") (pin "4") (pinfunction "4_4") (pintype "passive"))
      (node (ref "P6") (pin "6") (pinfunction "6_6") (pintype "passive"))
      (node (ref "P6") (pin "8") (pinfunction "8_8") (pintype "passive"))
      (node (ref "R43") (pin "2") (pinfunction "2_2") (pintype "passive"))
      (node (ref "R44") (pin "2") (pinfunction "2_2") (pintype "passive"))
      (node (ref "U10") (pin "9") (pinfunction "COM_9") (pintype "passive"))
    )
    (net (code "68") (name "/X_LIM") (class "Default")
      (node (ref "P16") (pin "7") (pinfunction "7_7") (pintype "passive"))
      (node (ref "U9") (pin "20") (pinfunction "A6_20") (pintype "bidirectional"))
    )
    (net (code "69") (name "/Y_LIM") (class "Default")
      (node (ref "P16") (pin "6") (pinfunction "6_6") (pintype "passive"))
      (node (ref "U9") (pin "21") (pinfunction "A7_21") (pintype "bidirectional"))
    )
    (net (code "70") (name "/Z_LIM") (class "Default")
      (node (ref "P16") (pin "5") (pinfunction "5_5") (pintype "passive"))
      (node (ref "U9") (pin "22") (pinfunction "A8_22") (pintype "bidirectional"))
    )
    (net (code "71") (name "GND") (class "Default")
      (node (ref "A1") (pin "14") (pinfunction "GND[4]_14") (pintype "power_in"))
      (node (ref "A1") (pin "20") (pinfunction "GND[5]_20") (pintype "power_in"))
      (node (ref "A1") (pin "25") (pinfunction "GND[2]_25") (pintype "power_in"))
      (node (ref "A1") (pin "30") (pinfunction "GND[6]_30") (pintype "power_in"))
      (node (ref "A1") (pin "34") (pinfunction "GND[7]_34") (pintype "power_in"))
      (node (ref "A1") (pin "39") (pinfunction "GND[3]_39") (pintype "power_in"))
      (node (ref "A1") (pin "6") (pinfunction "GND[8]_6") (pintype "power_in"))
      (node (ref "A1") (pin "9") (pinfunction "GND[1]_9") (pintype "power_in"))
      (node (ref "C10") (pin "1") (pinfunction "1_1") (pintype "passive"))
      (node (ref "C11") (pin "1") (pinfunction "1_1") (pintype "passive"))
      (node (ref "C12") (pin "1") (pinfunction "1_1") (pintype "passive"))
      (node (ref "C13") (pin "1") (pinfunction "1_1") (pintype "passive"))
      (node (ref "C14") (pin "2") (pinfunction "2_2") (pintype "passive"))
      (node (ref "C15") (pin "1") (pinfunction "1_1") (pintype "passive"))
      (node (ref "C16") (pin "1") (pinfunction "1_1") (pintype "passive"))
      (node (ref "C17") (pin "1") (pinfunction "1_1") (pintype "passive"))
      (node (ref "C18") (pin "1") (pinfunction "1_1") (pintype "passive"))
      (node (ref "C19") (pin "1") (pinfunction "1_1") (pintype "passive"))
      (node (ref "C7") (pin "1") (pinfunction "1_1") (pintype "passive"))
      (node (ref "C8") (pin "1") (pinfunction "1_1") (pintype "passive"))
      (node (ref "C9") (pin "1") (pinfunction "1_1") (pintype "passive"))
      (node (ref "D13") (pin "1") (pinfunction "A_1") (pintype "passive"))
      (node (ref "P10") (pin "5") (pinfunction "5_5") (pintype "passive"))
      (node (ref "P12") (pin "1") (pinfunction "1_1") (pintype "passive"))
      (node (ref "P13") (pin "4") (pinfunction "4_4") (pintype "passive"))
      (node (ref "P16") (pin "15") (pinfunction "15_15") (pintype "passive"))
      (node (ref "P16") (pin "2") (pinfunction "2_2") (pintype "passive"))
      (node (ref "P17") (pin "1") (pinfunction "1_1") (pintype "passive"))
      (node (ref "P18") (pin "3") (pinfunction "3_3") (pintype "passive"))
      (node (ref "P19") (pin "4") (pinfunction "4_4") (pintype "passive"))
      (node (ref "P19") (pin "5") (pinfunction "5_5") (pintype "passive"))
      (node (ref "P7") (pin "10") (pinfunction "GC_10") (pintype "passive"))
      (node (ref "P7") (pin "15") (pinfunction "SHIELD_15") (pintype "passive"))
      (node (ref "P7") (pin "16") (pinfunction "SHIELD_16") (pintype "passive"))
      (node (ref "P7") (pin "8") (pinfunction "GND_8") (pintype "power_in"))
      (node (ref "P8") (pin "A2") (pinfunction "A2_A2") (pintype "passive"))
      (node (ref "Q12") (pin "2") (pinfunction "E_2") (pintype "passive"))
      (node (ref "Q13") (pin "3") (pinfunction "C_3") (pintype "passive"))
      (node (ref "Q14") (pin "3") (pinfunction "C_3") (pintype "passive"))
      (node (ref "R45") (pin "1") (pinfunction "1_1") (pintype "passive"))
      (node (ref "R46") (pin "1") (pinfunction "1_1") (pintype "passive"))
      (node (ref "R52") (pin "1") (pinfunction "1_1") (pintype "passive"))
      (node (ref "U10") (pin "8") (pinfunction "GND_8") (pintype "power_in"))
      (node (ref "U11") (pin "7") (pinfunction "GND_7") (pintype "power_in"))
      (node (ref "U12") (pin "1") (pinfunction "A0_1") (pintype "input"))
      (node (ref "U12") (pin "2") (pinfunction "A1_2") (pintype "input"))
      (node (ref "U12") (pin "3") (pinfunction "A2_3") (pintype "input"))
      (node (ref "U12") (pin "4") (pinfunction "VSS_4") (pintype "power_in"))
      (node (ref "U12") (pin "7") (pinfunction "WP_7") (pintype "input"))
      (node (ref "U9") (pin "GND1") (pinfunction "GND_GND1") (pintype "power_in"))
      (node (ref "U9") (pin "GND2") (pinfunction "GND_GND2") (pintype "power_in"))
      (node (ref "U9") (pin "GND3") (pinfunction "GND_GND3") (pintype "power_in"))
      (node (ref "U9") (pin "GND4") (pinfunction "GND_GND4") (pintype "power_in"))
      (node (ref "U9") (pin "GND5") (pinfunction "GND_GND5") (pintype "power_in"))
      (node (ref "U9") (pin "USB_GND1") (pinfunction "USB_GND_USB_GND1") (pintype "power_in"))
      (node (ref "U9") (pin "USB_GND2") (pinfunction "USB_GND_USB_GND2") (pintype "power_in"))
      (node (ref "VR1") (pin "2") (pinfunction "GND_2") (pintype "passive"))
    )
    (net (code "72") (name "Net-(A1-5V[1])") (class "Default")
      (node (ref "A1") (pin "2") (pinfunction "5V[1]_2") (pintype "power_in"))
      (node (ref "A1") (pin "4") (pinfunction "5V[2]_4") (pintype "power_in"))
      (node (ref "D17") (pin "2") (pinfunction "K_2") (pintype "passive"))
    )
    (net (code "73") (name "Net-(D11-PadK)") (class "Default")
      (node (ref "D11") (pin "K") (pinfunction "K_K") (pintype "passive"))
      (node (ref "R45") (pin "2") (pinfunction "2_2") (pintype "passive"))
    )
    (net (code "74") (name "Net-(D12-PadK)") (class "Default")
      (node (ref "D12") (pin "K") (pinfunction "K_K") (pintype "passive"))
      (node (ref "R46") (pin "2") (pinfunction "2_2") (pintype "passive"))
    )
    (net (code "75") (name "Net-(D14-PadA)") (class "Default")
      (node (ref "D14") (pin "A") (pinfunction "A_A") (pintype "passive"))
      (node (ref "J10") (pin "2") (pinfunction "2_2") (pintype "passive"))
      (node (ref "R50") (pin "1") (pinfunction "1_1") (pintype "passive"))
      (node (ref "R51") (pin "1") (pinfunction "1_1") (pintype "passive"))
    )
    (net (code "76") (name "Net-(D14-PadK)") (class "Default")
      (node (ref "D14") (pin "K") (pinfunction "K_K") (pintype "passive"))
      (node (ref "R52") (pin "2") (pinfunction "2_2") (pintype "passive"))
    )
    (net (code "77") (name "Net-(D15-PadK)") (class "Default")
      (node (ref "D15") (pin "K") (pinfunction "K_K") (pintype "passive"))
      (node (ref "R55") (pin "2") (pinfunction "2_2") (pintype "passive"))
    )
    (net (code "78") (name "Net-(D16-PadK)") (class "Default")
      (node (ref "D16") (pin "K") (pinfunction "K_K") (pintype "passive"))
      (node (ref "R56") (pin "2") (pinfunction "2_2") (pintype "passive"))
    )
    (net (code "79") (name "Net-(FUSE1-Pad1)") (class "Default")
      (node (ref "FUSE1") (pin "1") (pinfunction "1_1") (pintype "passive"))
      (node (ref "P8") (pin "A1") (pinfunction "A1_A1") (pintype "passive"))
    )
    (net (code "80") (name "Net-(P7-P4)") (class "Default")
      (node (ref "C7") (pin "2") (pinfunction "2_2") (pintype "passive"))
      (node (ref "P7") (pin "4") (pinfunction "P4_4") (pintype "passive"))
      (node (ref "P7") (pin "5") (pinfunction "P5_5") (pintype "passive"))
    )
    (net (code "81") (name "Net-(Q12-B)") (class "Default")
      (node (ref "Q12") (pin "1") (pinfunction "B_1") (pintype "passive"))
      (node (ref "R51") (pin "2") (pinfunction "2_2") (pintype "passive"))
    )
    (net (code "82") (name "Net-(Q12-C)") (class "Default")
      (node (ref "J11") (pin "1") (pinfunction "1_1") (pintype "passive"))
      (node (ref "J12") (pin "1") (pinfunction "1_1") (pintype "passive"))
      (node (ref "J13") (pin "1") (pinfunction "1_1") (pintype "passive"))
      (node (ref "J14") (pin "1") (pinfunction "1_1") (pintype "passive"))
      (node (ref "Q12") (pin "3") (pinfunction "C_3") (pintype "passive"))
    )
    (net (code "83") (name "Net-(Q13-B)") (class "Default")
      (node (ref "Q13") (pin "1") (pinfunction "B_1") (pintype "passive"))
      (node (ref "R58") (pin "1") (pinfunction "1_1") (pintype "passive"))
    )
    (net (code "84") (name "Net-(Q13-E)") (class "Default")
      (node (ref "Q13") (pin "2") (pinfunction "E_2") (pintype "passive"))
      (node (ref "R56") (pin "1") (pinfunction "1_1") (pintype "passive"))
    )
    (net (code "85") (name "Net-(Q14-B)") (class "Default")
      (node (ref "Q14") (pin "1") (pinfunction "B_1") (pintype "passive"))
      (node (ref "R60") (pin "2") (pinfunction "2_2") (pintype "passive"))
    )
    (net (code "86") (name "Net-(Q14-E)") (class "Default")
      (node (ref "Q14") (pin "2") (pinfunction "E_2") (pintype "passive"))
      (node (ref "R55") (pin "1") (pinfunction "1_1") (pintype "passive"))
    )
    (net (code "87") (name "Net-(U11A-A)") (class "Default")
      (node (ref "C15") (pin "2") (pinfunction "2_2") (pintype "passive"))
      (node (ref "R53") (pin "1") (pinfunction "1_1") (pintype "passive"))
      (node (ref "R54") (pin "2") (pinfunction "2_2") (pintype "passive"))
      (node (ref "U11") (pin "1") (pinfunction "A_1") (pintype "input"))
    )
    (net (code "88") (name "Net-(U11B-A)") (class "Default")
      (node (ref "C16") (pin "2") (pinfunction "2_2") (pintype "passive"))
      (node (ref "R57") (pin "1") (pinfunction "1_1") (pintype "passive"))
      (node (ref "R59") (pin "2") (pinfunction "2_2") (pintype "passive"))
      (node (ref "U11") (pin "3") (pinfunction "A_3") (pintype "input"))
    )
    (net (code "89") (name "Net-(U11C-A)") (class "Default")
      (node (ref "C17") (pin "2") (pinfunction "2_2") (pintype "passive"))
      (node (ref "R61") (pin "1") (pinfunction "1_1") (pintype "passive"))
      (node (ref "R62") (pin "2") (pinfunction "2_2") (pintype "passive"))
      (node (ref "U11") (pin "5") (pinfunction "A_5") (pintype "input"))
    )
    (net (code "90") (name "Net-(U11D-A)") (class "Default")
      (node (ref "C18") (pin "2") (pinfunction "2_2") (pintype "passive"))
      (node (ref "R63") (pin "1") (pinfunction "1_1") (pintype "passive"))
      (node (ref "R64") (pin "2") (pinfunction "2_2") (pintype "passive"))
      (node (ref "U11") (pin "9") (pinfunction "A_9") (pintype "input"))
    )
    (net (code "91") (name "Net-(U11E-Y)") (class "Default")
      (node (ref "J10") (pin "1") (pinfunction "1_1") (pintype "passive"))
      (node (ref "U11") (pin "10") (pinfunction "Y_10") (pintype "output"))
    )
    (net (code "92") (name "PI+3.3V") (class "Default")
      (node (ref "A1") (pin "1") (pinfunction "3V3[1]_1") (pintype "power_in"))
      (node (ref "P12") (pin "5") (pinfunction "5_5") (pintype "passive"))
    )
    (net (code "93") (name "RELAY_VCC") (class "Default")
      (node (ref "P9") (pin "2") (pinfunction "2_2") (pintype "passive"))
      (node (ref "R43") (pin "1") (pinfunction "1_1") (pintype "passive"))
    )
    (net (code "94") (name "STEPPER_VCC") (class "Default")
      (node (ref "L1") (pin "2") (pinfunction "2_2") (pintype "passive"))
    )
    (net (code "95") (name "VDD") (class "Default")
      (node (ref "U11") (pin "14") (pinfunction "VDD_14") (pintype "power_in"))
    )
    (net (code "96") (name "unconnected-(A1-3V3[2]-Pad17)") (class "Default")
      (node (ref "A1") (pin "17") (pinfunction "3V3[2]_17") (pintype "power_in"))
    )
    (net (code "97") (name "unconnected-(A1-GEN5{slash}GPIO24-Pad18)") (class "Default")
      (node (ref "A1") (pin "18") (pinfunction "GEN5/GPIO24_18") (pintype "bidirectional"))
    )
    (net (code "98") (name "unconnected-(A1-GEN{slash}6GPIO25-Pad22)") (class "Default")
      (node (ref "A1") (pin "22") (pinfunction "GEN/6GPIO25_22") (pintype "bidirectional"))
    )
    (net (code "99") (name "unconnected-(A1-GPIO9{slash}MISO-Pad21)") (class "Default")
      (node (ref "A1") (pin "21") (pinfunction "GPIO9/MISO_21") (pintype "bidirectional"))
    )
    (net (code "100") (name "unconnected-(A1-GPIO10{slash}MOSI-Pad19)") (class "Default")
      (node (ref "A1") (pin "19") (pinfunction "GPIO10/MOSI_19") (pintype "bidirectional"))
    )
    (net (code "101") (name "unconnected-(A1-GPIO11{slash}SCLK-Pad23)") (class "Default")
      (node (ref "A1") (pin "23") (pinfunction "GPIO11/SCLK_23") (pintype "bidirectional"))
    )
    (net (code "102") (name "unconnected-(A1-ID_SD-Pad27)") (class "Default")
      (node (ref "A1") (pin "27") (pinfunction "ID_SD_27") (pintype "bidirectional"))
    )
    (net (code "103") (name "unconnected-(A1-~{CE0!{slash}GPIO8}-Pad24)") (class "Default")
      (node (ref "A1") (pin "24") (pinfunction "~{CE0!/GPIO8}_24") (pintype "bidirectional"))
    )
    (net (code "104") (name "unconnected-(P7-YA-Pad12)") (class "Default")
      (node (ref "P7") (pin "12") (pinfunction "YA_12") (pintype "passive+no_connect"))
    )
    (net (code "105") (name "unconnected-(P7-YC-Pad11)") (class "Default")
      (node (ref "P7") (pin "11") (pinfunction "YC_11") (pintype "passive+no_connect"))
    )
    (net (code "106") (name "unconnected-(P16-Pad3)") (class "Default")
      (node (ref "P16") (pin "3") (pinfunction "3_3") (pintype "passive+no_connect"))
    )
    (net (code "107") (name "unconnected-(P19-Pad2)") (class "Default")
      (node (ref "P19") (pin "2") (pinfunction "2_2") (pintype "passive"))
    )
    (net (code "108") (name "unconnected-(P19-Pad3)") (class "Default")
      (node (ref "P19") (pin "3") (pinfunction "3_3") (pintype "passive"))
    )
    (net (code "109") (name "unconnected-(U9-3.3V-Pad3.3V_2)") (class "Default")
      (node (ref "U9") (pin "3.3V_2") (pinfunction "3.3V_3.3V_2") (pintype "power_in+no_connect"))
    )
    (net (code "110") (name "unconnected-(U9-PadD+)") (class "Default")
      (node (ref "U9") (pin "D+") (pinfunction "D+_D+") (pintype "bidirectional+no_connect"))
    )
    (net (code "111") (name "unconnected-(U9-PadD-)") (class "Default")
      (node (ref "U9") (pin "D-") (pinfunction "D-_D-") (pintype "bidirectional+no_connect"))
    )
    (net (code "112") (name "unconnected-(U9-PadPROGRAM)") (class "Default")
      (node (ref "U9") (pin "PROGRAM") (pinfunction "PROGRAM_PROGRAM") (pintype "bidirectional"))
    )
    (net (code "113") (name "unconnected-(U9-PadVBAT)") (class "Default")
      (node (ref "U9") (pin "VBAT") (pinfunction "VBAT_VBAT") (pintype "passive+no_connect"))
    )
    (net (code "114") (name "unconnected-(U9-PadVUSB)") (class "Default")
      (node (ref "U9") (pin "VUSB") (pinfunction "VUSB_VUSB") (pintype "passive+no_connect"))
    )
    (net (code "115") (name "unconnected-(U10-IN5-Pad5)") (class "Default")
      (node (ref "U10") (pin "5") (pinfunction "IN5_5") (pintype "input+no_connect"))
    )
    (net (code "116") (name "unconnected-(U10-IN6-Pad6)") (class "Default")
      (node (ref "U10") (pin "6") (pinfunction "IN6_6") (pintype "input+no_connect"))
    )
    (net (code "117") (name "unconnected-(U10-IN7-Pad7)") (class "Default")
      (node (ref "U10") (pin "7") (pinfunction "IN7_7") (pintype "input+no_connect"))
    )
    (net (code "118") (name "unconnected-(U10-OUT5-Pad12)") (class "Default")
      (node (ref "U10") (pin "12") (pinfunction "OUT5_12") (pintype "open_collector+no_connect"))
    )
    (net (code "119") (name "unconnected-(U10-OUT6-Pad11)") (class "Default")
      (node (ref "U10") (pin "11") (pinfunction "OUT6_11") (pintype "open_collector+no_connect"))
    )
    (net (code "120") (name "unconnected-(U10-OUT7-Pad10)") (class "Default")
      (node (ref "U10") (pin "10") (pinfunction "OUT7_10") (pintype "open_collector+no_connect"))
    )
  )
)
